# MEM_P2P_1.net
KiCad netlist of a schematic drawn in EAGLE
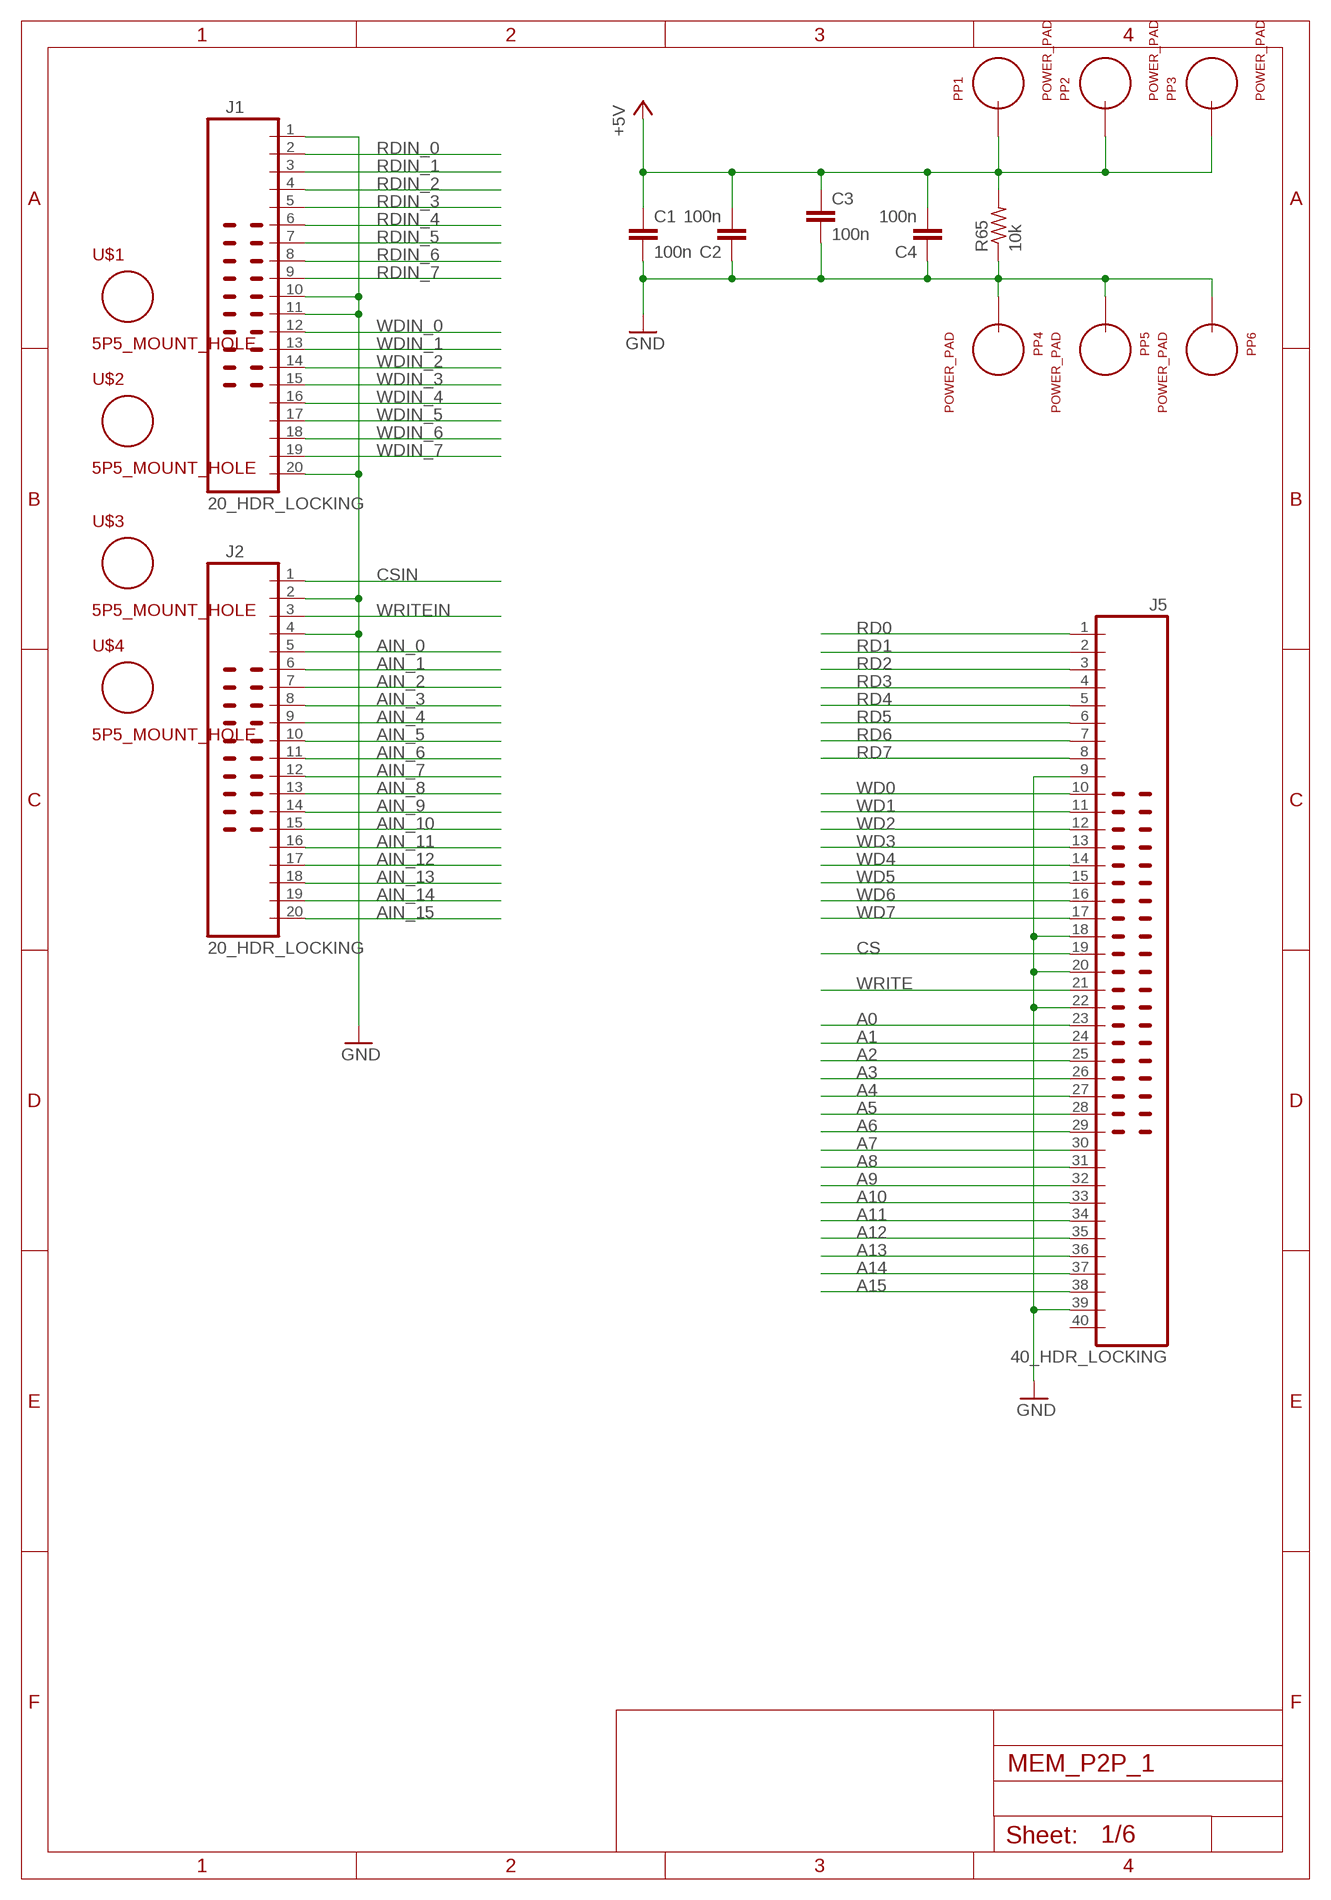
[diagram p0: schematic, sheet 1]
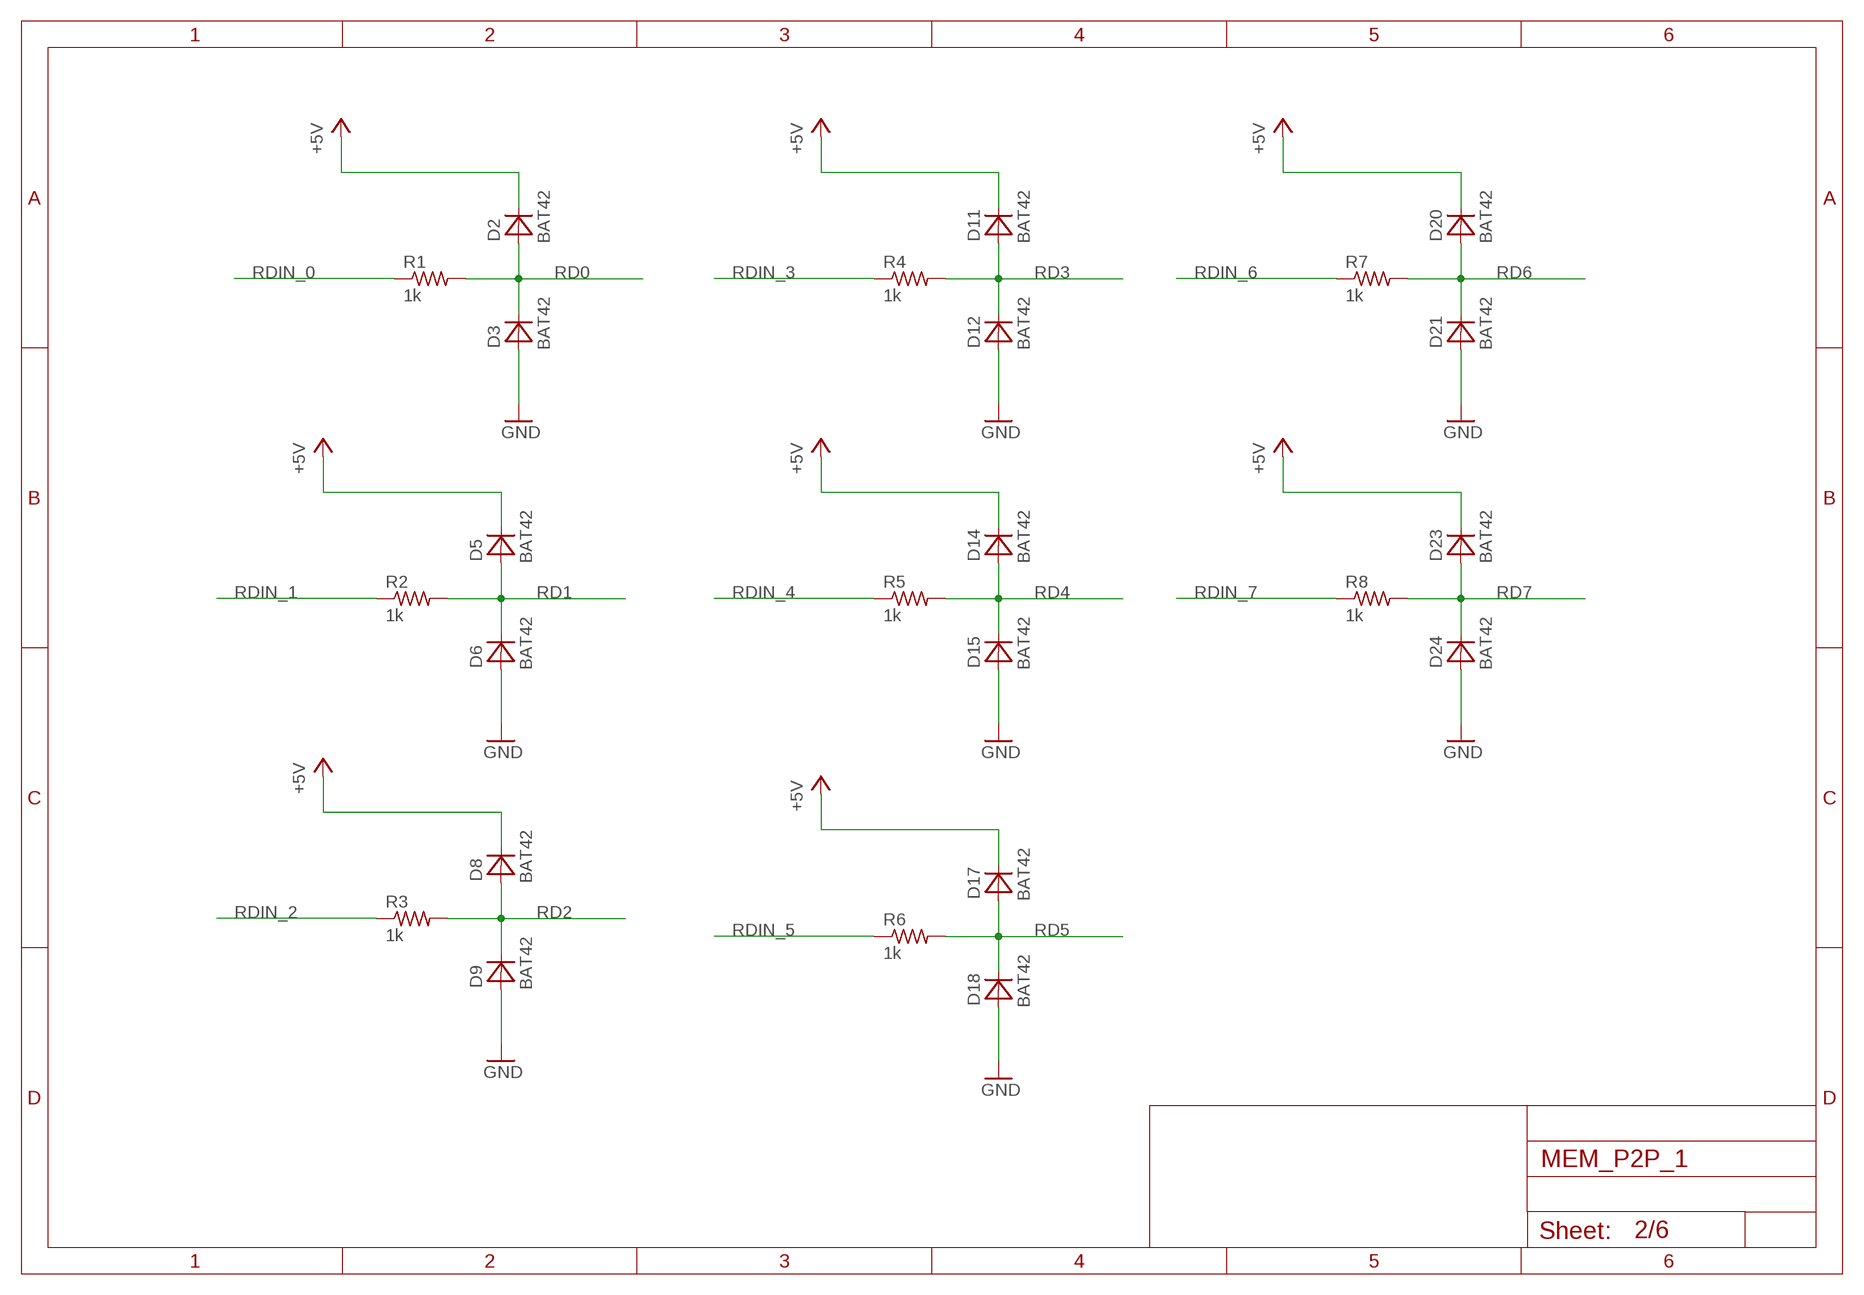
[diagram p1: schematic, sheet 2]
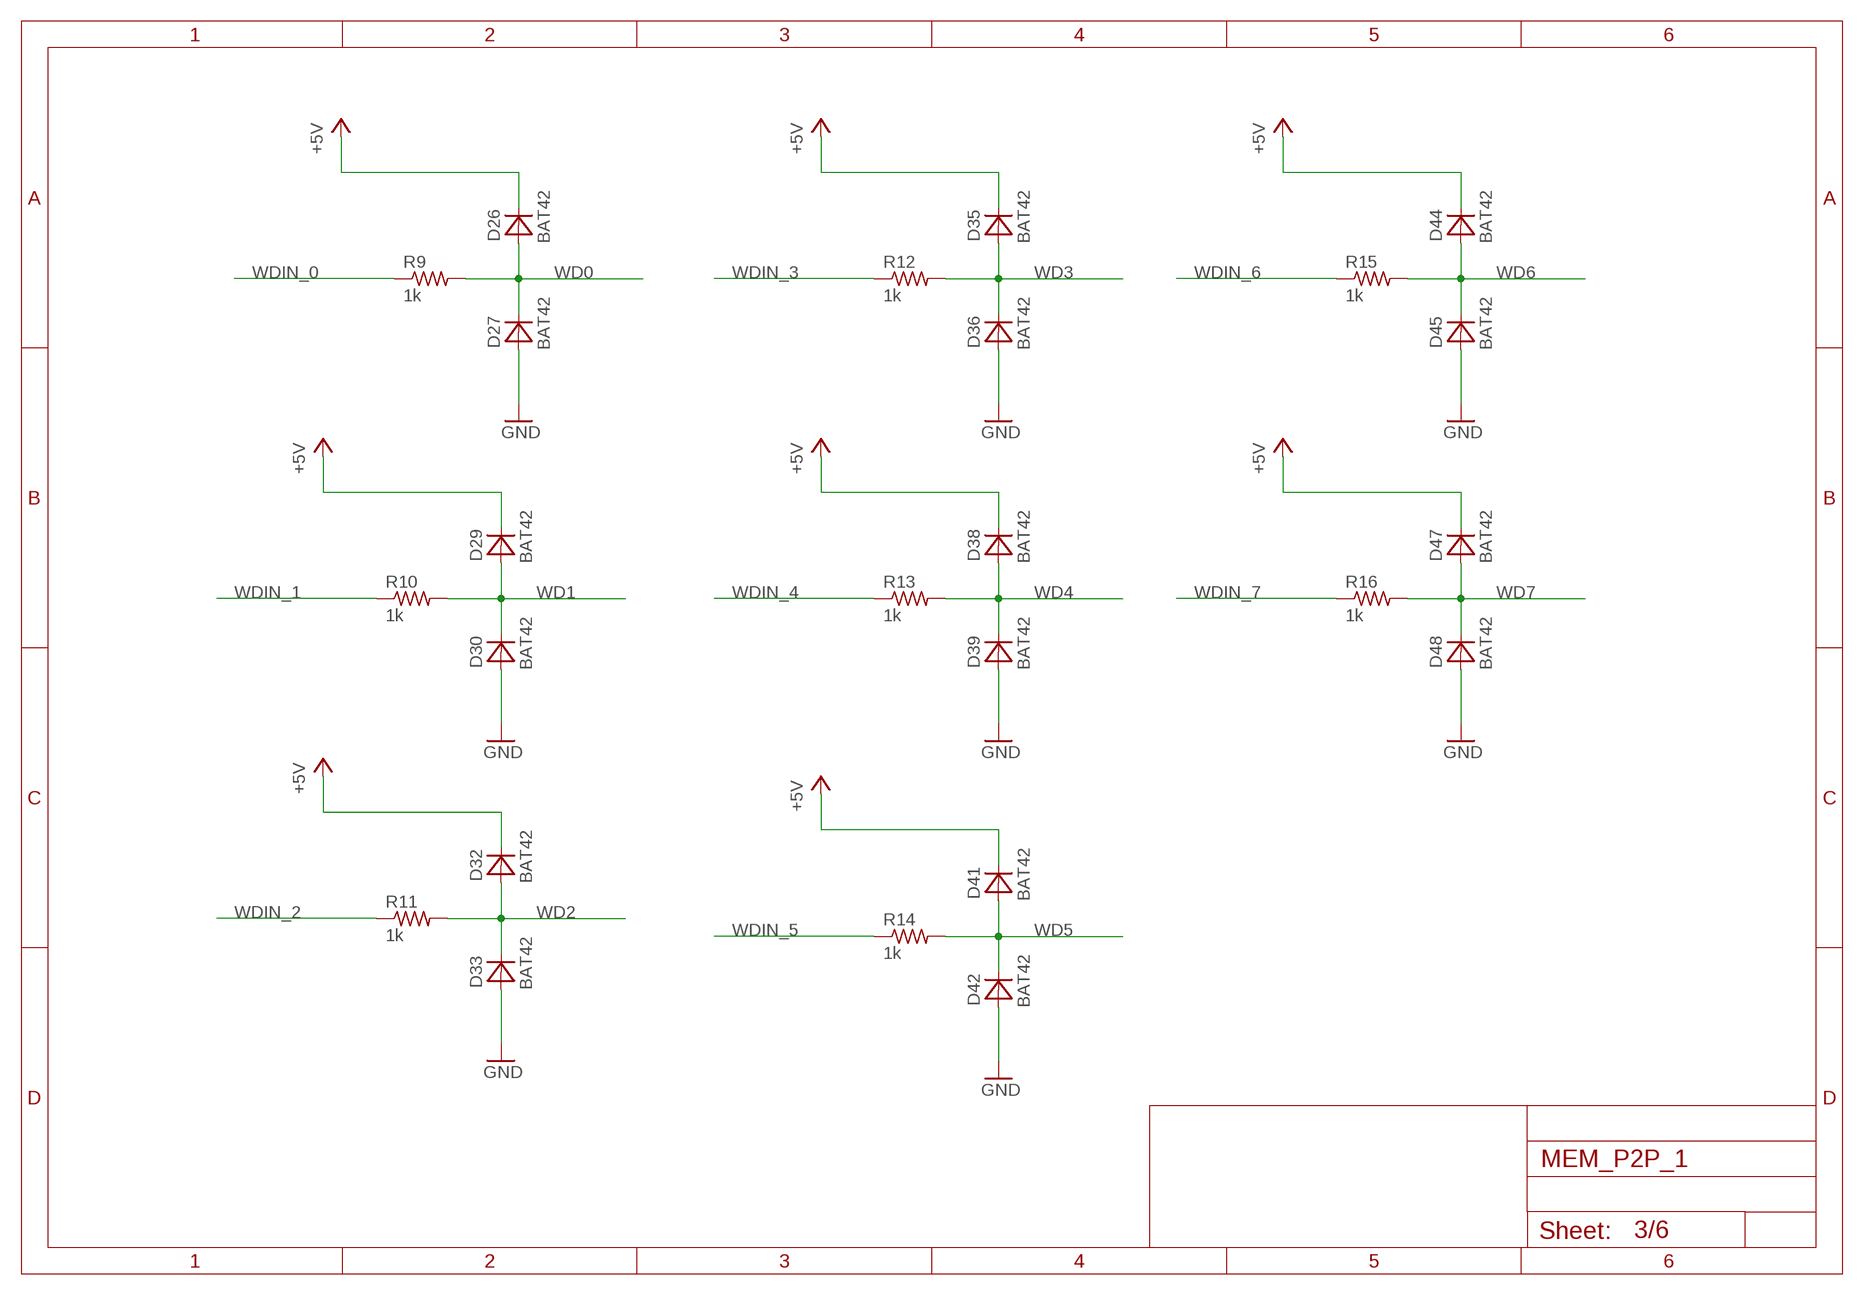
[diagram p2: schematic, sheet 3]
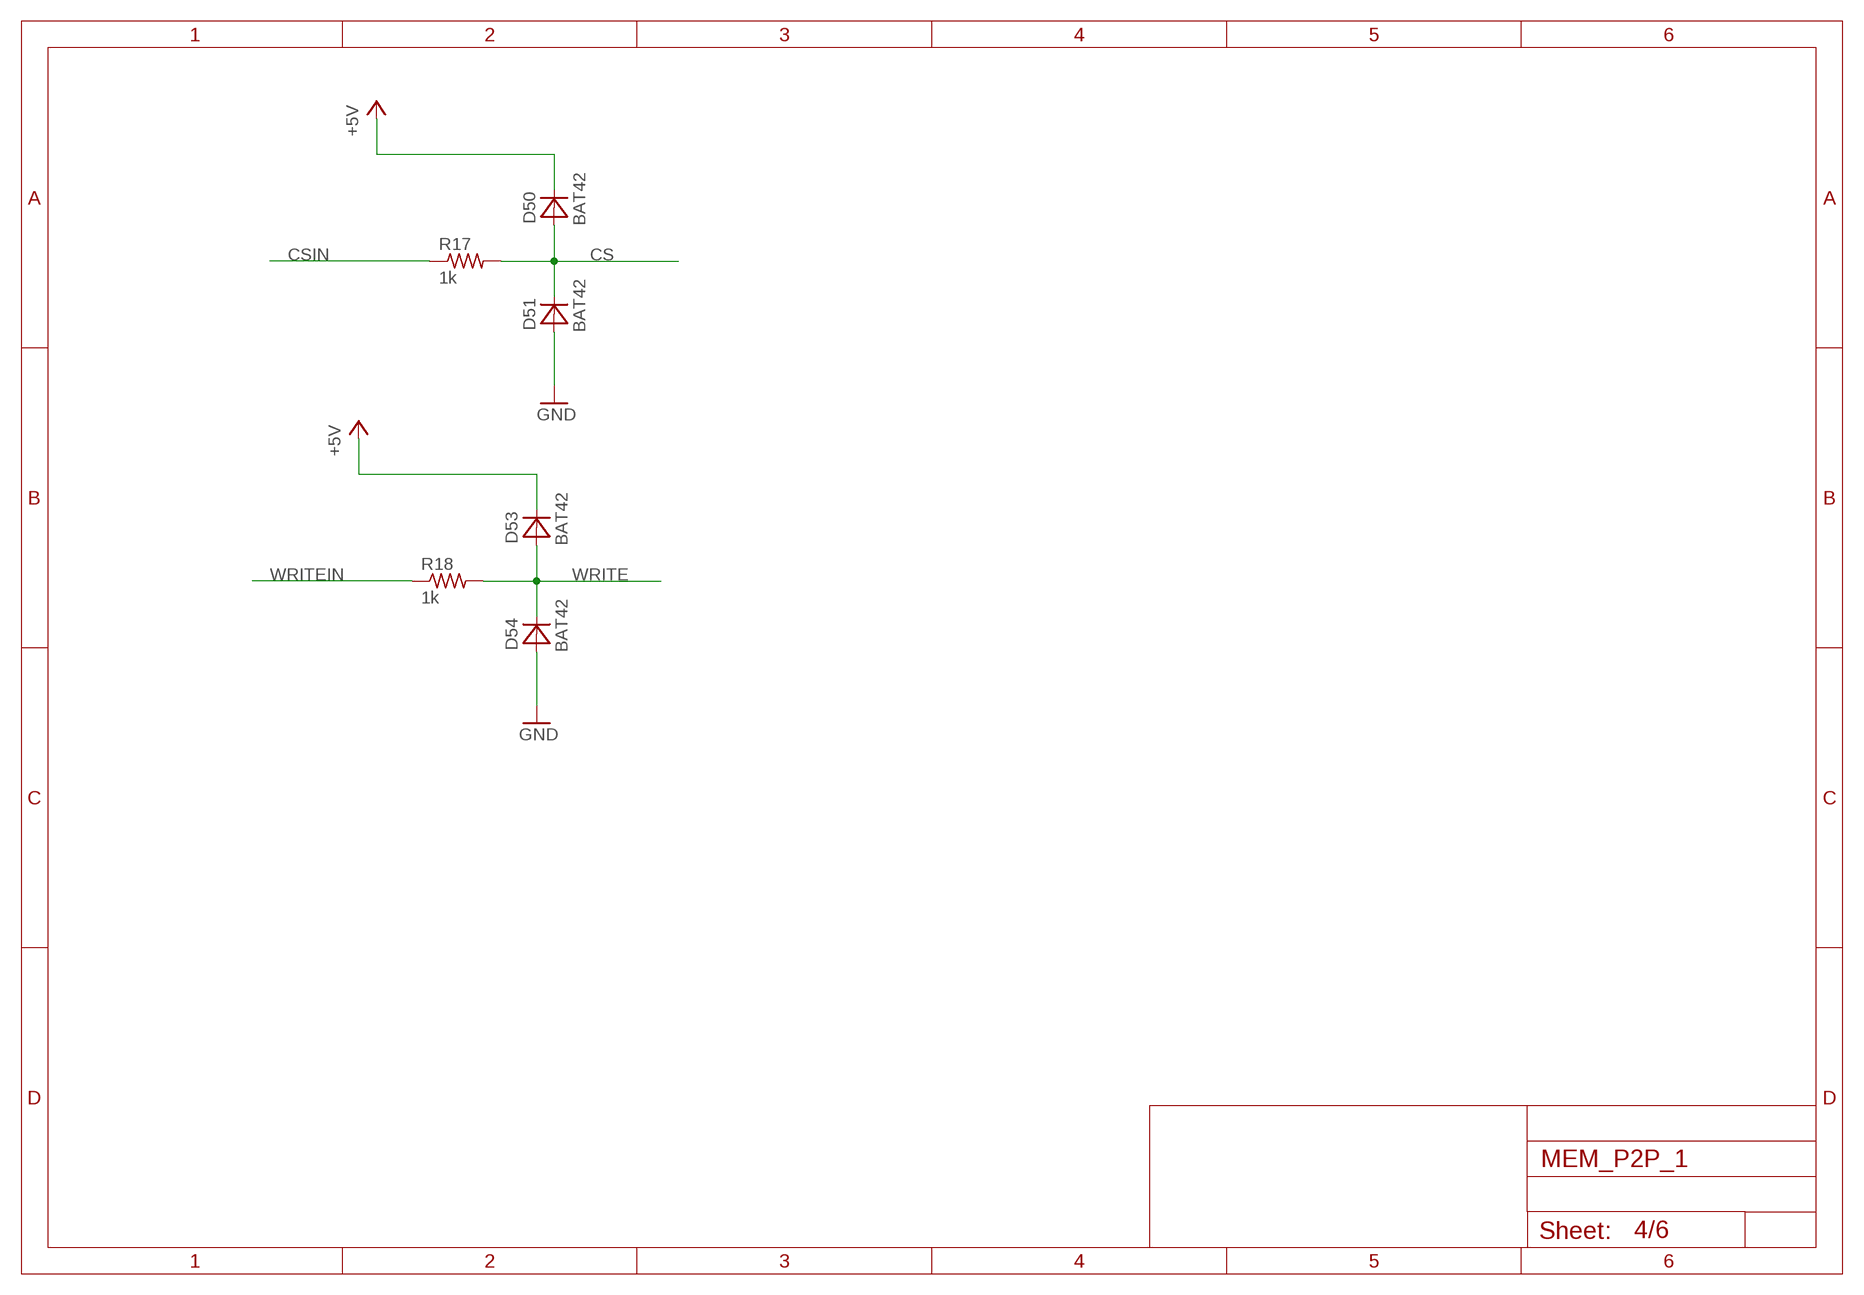
[diagram p3: schematic, sheet 4]
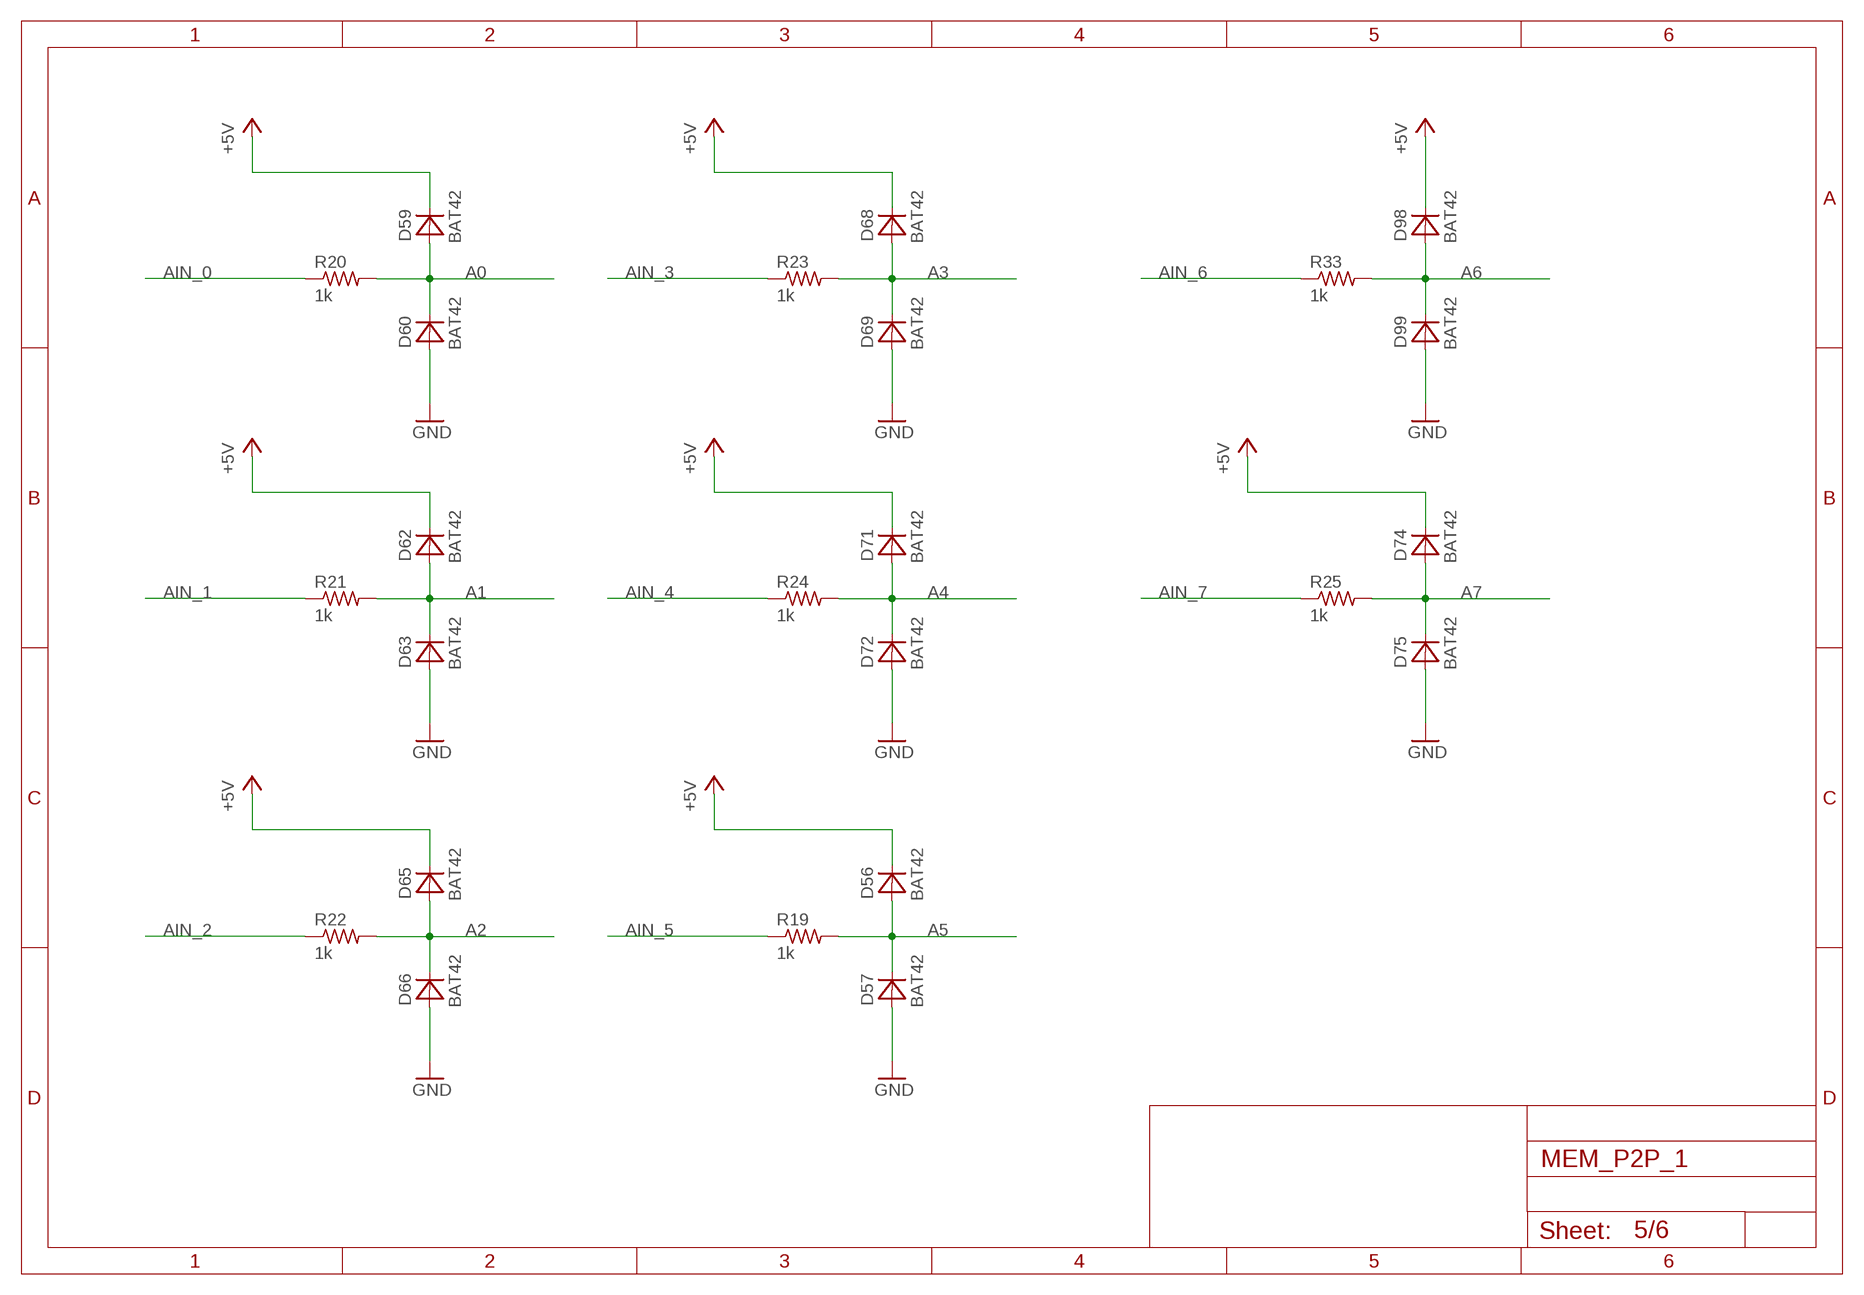
[diagram p4: schematic, sheet 5]
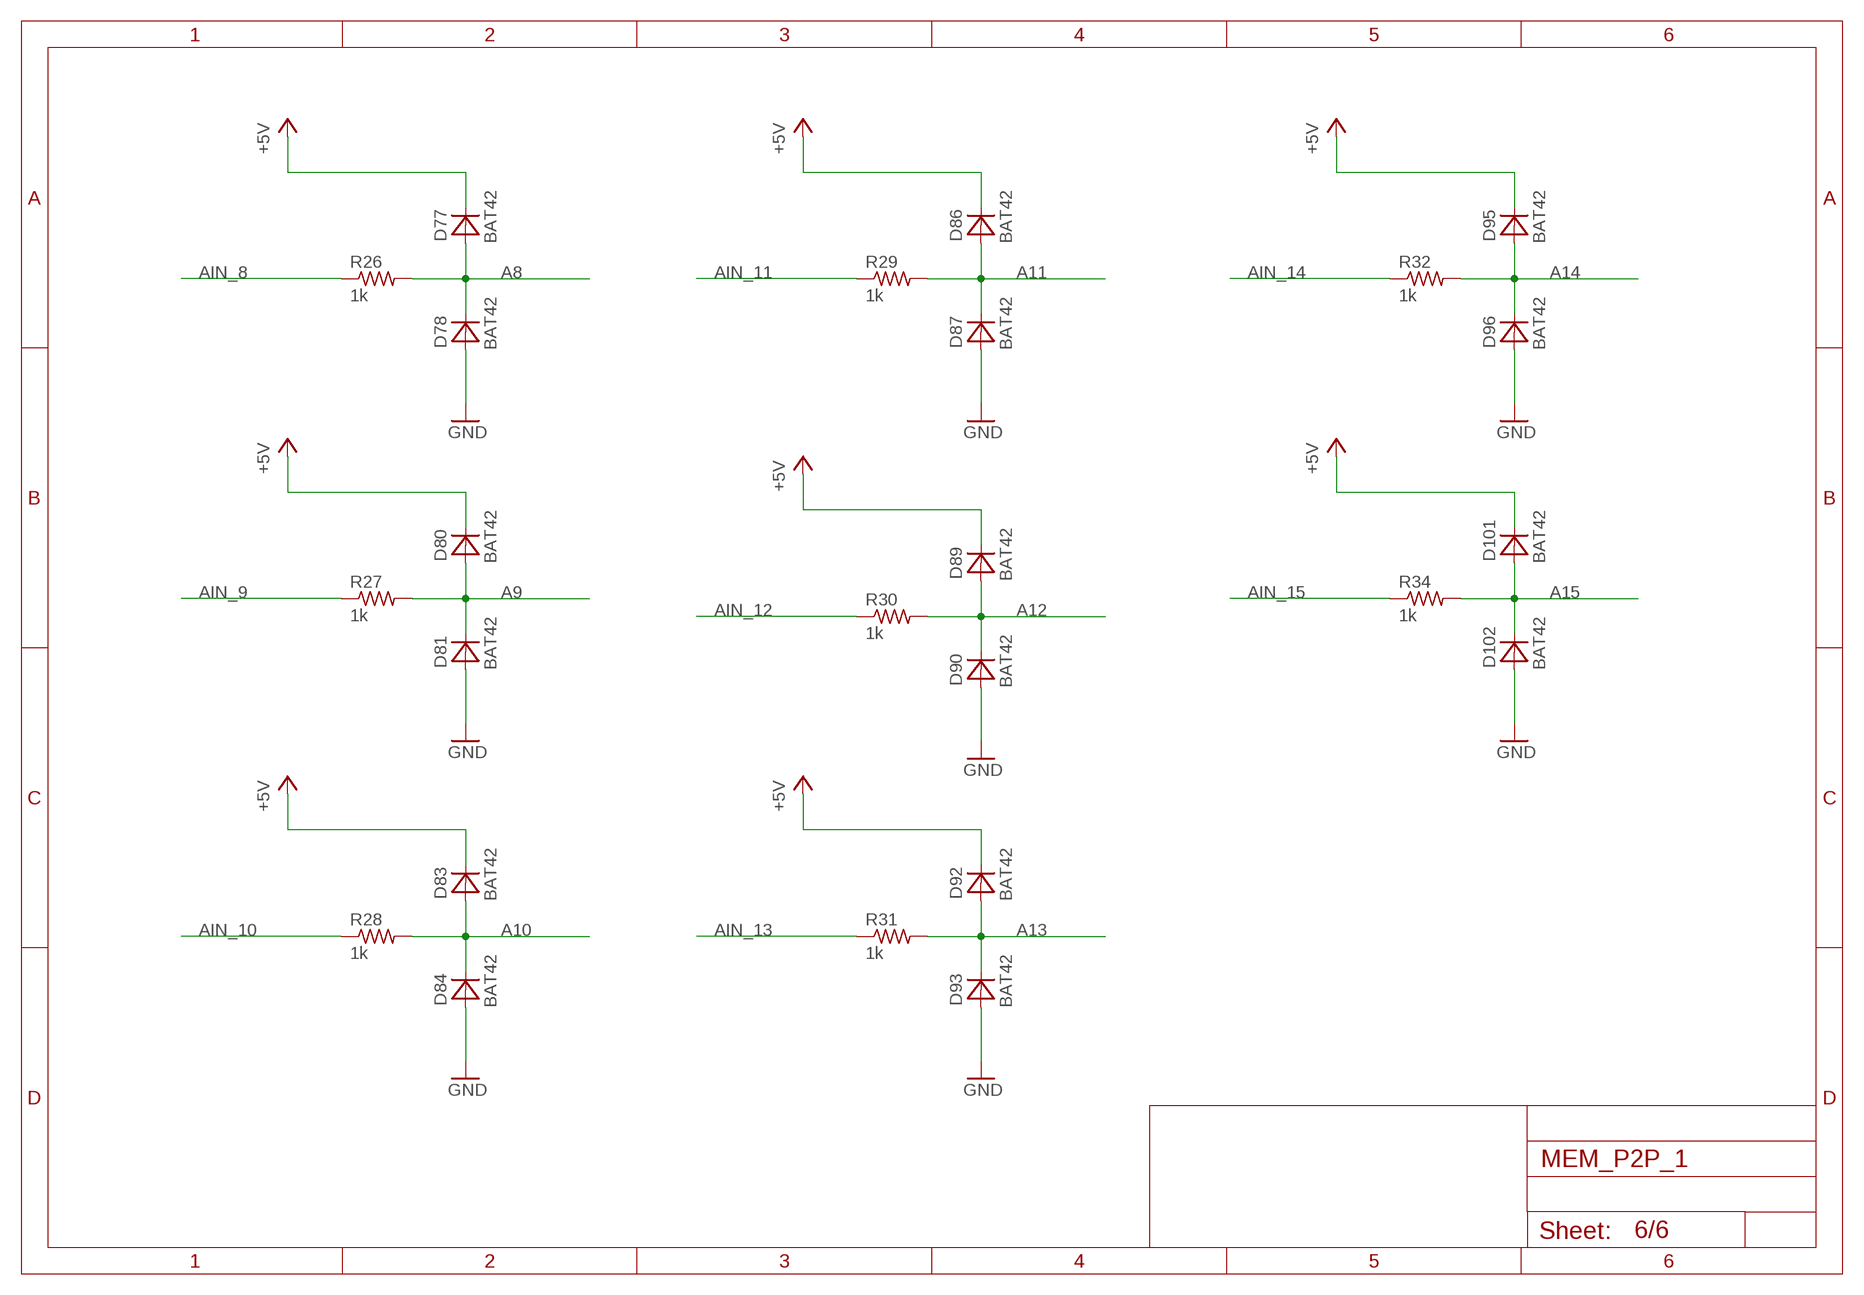
[diagram p5: schematic, sheet 6]

(export (version "E")
  (design (tool "Eeschema 10.0.6"))
  (components
    (comp (ref "D26")
      (value "BAT42")
      (footprint "eagle-import:DO34-5")
      (libsource (lib "eagle-import") (part "BAT42"))
    )
    (comp (ref "D27")
      (value "BAT42")
      (footprint "eagle-import:DO34-5")
      (libsource (lib "eagle-import") (part "BAT42"))
    )
    (comp (ref "D29")
      (value "BAT42")
      (footprint "eagle-import:DO34-5")
      (libsource (lib "eagle-import") (part "BAT42"))
    )
    (comp (ref "D30")
      (value "BAT42")
      (footprint "eagle-import:DO34-5")
      (libsource (lib "eagle-import") (part "BAT42"))
    )
    (comp (ref "D32")
      (value "BAT42")
      (footprint "eagle-import:DO34-5")
      (libsource (lib "eagle-import") (part "BAT42"))
    )
    (comp (ref "D33")
      (value "BAT42")
      (footprint "eagle-import:DO34-5")
      (libsource (lib "eagle-import") (part "BAT42"))
    )
    (comp (ref "D35")
      (value "BAT42")
      (footprint "eagle-import:DO34-5")
      (libsource (lib "eagle-import") (part "BAT42"))
    )
    (comp (ref "D36")
      (value "BAT42")
      (footprint "eagle-import:DO34-5")
      (libsource (lib "eagle-import") (part "BAT42"))
    )
    (comp (ref "D38")
      (value "BAT42")
      (footprint "eagle-import:DO34-5")
      (libsource (lib "eagle-import") (part "BAT42"))
    )
    (comp (ref "D39")
      (value "BAT42")
      (footprint "eagle-import:DO34-5")
      (libsource (lib "eagle-import") (part "BAT42"))
    )
    (comp (ref "D41")
      (value "BAT42")
      (footprint "eagle-import:DO34-5")
      (libsource (lib "eagle-import") (part "BAT42"))
    )
    (comp (ref "D42")
      (value "BAT42")
      (footprint "eagle-import:DO34-5")
      (libsource (lib "eagle-import") (part "BAT42"))
    )
    (comp (ref "D44")
      (value "BAT42")
      (footprint "eagle-import:DO34-5")
      (libsource (lib "eagle-import") (part "BAT42"))
    )
    (comp (ref "D45")
      (value "BAT42")
      (footprint "eagle-import:DO34-5")
      (libsource (lib "eagle-import") (part "BAT42"))
    )
    (comp (ref "D47")
      (value "BAT42")
      (footprint "eagle-import:DO34-5")
      (libsource (lib "eagle-import") (part "BAT42"))
    )
    (comp (ref "D48")
      (value "BAT42")
      (footprint "eagle-import:DO34-5")
      (libsource (lib "eagle-import") (part "BAT42"))
    )
    (comp (ref "R9")
      (value "1k")
      (footprint "eagle-import:R_P2INCH")
      (libsource (lib "eagle-import") (part "R_P2INCH"))
    )
    (comp (ref "R10")
      (value "1k")
      (footprint "eagle-import:R_P2INCH")
      (libsource (lib "eagle-import") (part "R_P2INCH"))
    )
    (comp (ref "R11")
      (value "1k")
      (footprint "eagle-import:R_P2INCH")
      (libsource (lib "eagle-import") (part "R_P2INCH"))
    )
    (comp (ref "R12")
      (value "1k")
      (footprint "eagle-import:R_P2INCH")
      (libsource (lib "eagle-import") (part "R_P2INCH"))
    )
    (comp (ref "R13")
      (value "1k")
      (footprint "eagle-import:R_P2INCH")
      (libsource (lib "eagle-import") (part "R_P2INCH"))
    )
    (comp (ref "R14")
      (value "1k")
      (footprint "eagle-import:R_P2INCH")
      (libsource (lib "eagle-import") (part "R_P2INCH"))
    )
    (comp (ref "R15")
      (value "1k")
      (footprint "eagle-import:R_P2INCH")
      (libsource (lib "eagle-import") (part "R_P2INCH"))
    )
    (comp (ref "R16")
      (value "1k")
      (footprint "eagle-import:R_P2INCH")
      (libsource (lib "eagle-import") (part "R_P2INCH"))
    )
    (comp (ref "C1")
      (value "100n")
      (footprint "eagle-import:CAP_P2INCH")
      (libsource (lib "eagle-import") (part "C_P2INCH"))
    )
    (comp (ref "C2")
      (value "100n")
      (footprint "eagle-import:CAP_P2INCH")
      (libsource (lib "eagle-import") (part "C_P2INCH"))
    )
    (comp (ref "C3")
      (value "100n")
      (footprint "eagle-import:CAP_P2INCH")
      (libsource (lib "eagle-import") (part "C_P2INCH"))
    )
    (comp (ref "C4")
      (value "100n")
      (footprint "eagle-import:CAP_P2INCH")
      (libsource (lib "eagle-import") (part "C_P2INCH"))
    )
    (comp (ref "J1")
      (value "20_HDR_LOCKING")
      (footprint "eagle-import:20_HDR_LOCKING")
      (libsource (lib "eagle-import") (part "20_HDR_LOCKING"))
    )
    (comp (ref "J2")
      (value "20_HDR_LOCKING")
      (footprint "eagle-import:20_HDR_LOCKING")
      (libsource (lib "eagle-import") (part "20_HDR_LOCKING"))
    )
    (comp (ref "J5")
      (value "40_HDR_LOCKING")
      (footprint "eagle-import:40_HDR_LOCKING")
      (libsource (lib "eagle-import") (part "40_HDR_LOCKING"))
    )
    (comp (ref "PP1")
      (value "POWER_PAD")
      (footprint "eagle-import:POWER_PAD")
      (libsource (lib "eagle-import") (part "POWER_PAD"))
    )
    (comp (ref "PP2")
      (value "POWER_PAD")
      (footprint "eagle-import:POWER_PAD")
      (libsource (lib "eagle-import") (part "POWER_PAD"))
    )
    (comp (ref "PP3")
      (value "POWER_PAD")
      (footprint "eagle-import:POWER_PAD")
      (libsource (lib "eagle-import") (part "POWER_PAD"))
    )
    (comp (ref "PP4")
      (value "POWER_PAD")
      (footprint "eagle-import:POWER_PAD")
      (libsource (lib "eagle-import") (part "POWER_PAD"))
    )
    (comp (ref "PP5")
      (value "POWER_PAD")
      (footprint "eagle-import:POWER_PAD")
      (libsource (lib "eagle-import") (part "POWER_PAD"))
    )
    (comp (ref "PP6")
      (value "POWER_PAD")
      (footprint "eagle-import:POWER_PAD")
      (libsource (lib "eagle-import") (part "POWER_PAD"))
    )
    (comp (ref "R65")
      (value "10k")
      (footprint "eagle-import:R_P2INCH")
      (libsource (lib "eagle-import") (part "R_P2INCH"))
    )
    (comp (ref "U$1")
      (value "5P5_MOUNT_HOLE")
      (footprint "eagle-import:5P5M_HOLE")
      (libsource (lib "eagle-import") (part "5P5_MOUNT_HOLE"))
    )
    (comp (ref "U$2")
      (value "5P5_MOUNT_HOLE")
      (footprint "eagle-import:5P5M_HOLE")
      (libsource (lib "eagle-import") (part "5P5_MOUNT_HOLE"))
    )
    (comp (ref "U$3")
      (value "5P5_MOUNT_HOLE")
      (footprint "eagle-import:5P5M_HOLE")
      (libsource (lib "eagle-import") (part "5P5_MOUNT_HOLE"))
    )
    (comp (ref "U$4")
      (value "5P5_MOUNT_HOLE")
      (footprint "eagle-import:5P5M_HOLE")
      (libsource (lib "eagle-import") (part "5P5_MOUNT_HOLE"))
    )
    (comp (ref "D56")
      (value "BAT42")
      (footprint "eagle-import:DO34-5")
      (libsource (lib "eagle-import") (part "BAT42"))
    )
    (comp (ref "D57")
      (value "BAT42")
      (footprint "eagle-import:DO34-5")
      (libsource (lib "eagle-import") (part "BAT42"))
    )
    (comp (ref "D59")
      (value "BAT42")
      (footprint "eagle-import:DO34-5")
      (libsource (lib "eagle-import") (part "BAT42"))
    )
    (comp (ref "D60")
      (value "BAT42")
      (footprint "eagle-import:DO34-5")
      (libsource (lib "eagle-import") (part "BAT42"))
    )
    (comp (ref "D62")
      (value "BAT42")
      (footprint "eagle-import:DO34-5")
      (libsource (lib "eagle-import") (part "BAT42"))
    )
    (comp (ref "D63")
      (value "BAT42")
      (footprint "eagle-import:DO34-5")
      (libsource (lib "eagle-import") (part "BAT42"))
    )
    (comp (ref "D65")
      (value "BAT42")
      (footprint "eagle-import:DO34-5")
      (libsource (lib "eagle-import") (part "BAT42"))
    )
    (comp (ref "D66")
      (value "BAT42")
      (footprint "eagle-import:DO34-5")
      (libsource (lib "eagle-import") (part "BAT42"))
    )
    (comp (ref "D68")
      (value "BAT42")
      (footprint "eagle-import:DO34-5")
      (libsource (lib "eagle-import") (part "BAT42"))
    )
    (comp (ref "D69")
      (value "BAT42")
      (footprint "eagle-import:DO34-5")
      (libsource (lib "eagle-import") (part "BAT42"))
    )
    (comp (ref "D71")
      (value "BAT42")
      (footprint "eagle-import:DO34-5")
      (libsource (lib "eagle-import") (part "BAT42"))
    )
    (comp (ref "D72")
      (value "BAT42")
      (footprint "eagle-import:DO34-5")
      (libsource (lib "eagle-import") (part "BAT42"))
    )
    (comp (ref "D74")
      (value "BAT42")
      (footprint "eagle-import:DO34-5")
      (libsource (lib "eagle-import") (part "BAT42"))
    )
    (comp (ref "D75")
      (value "BAT42")
      (footprint "eagle-import:DO34-5")
      (libsource (lib "eagle-import") (part "BAT42"))
    )
    (comp (ref "D98")
      (value "BAT42")
      (footprint "eagle-import:DO34-5")
      (libsource (lib "eagle-import") (part "BAT42"))
    )
    (comp (ref "D99")
      (value "BAT42")
      (footprint "eagle-import:DO34-5")
      (libsource (lib "eagle-import") (part "BAT42"))
    )
    (comp (ref "R19")
      (value "1k")
      (footprint "eagle-import:R_P2INCH")
      (libsource (lib "eagle-import") (part "R_P2INCH"))
    )
    (comp (ref "R20")
      (value "1k")
      (footprint "eagle-import:R_P2INCH")
      (libsource (lib "eagle-import") (part "R_P2INCH"))
    )
    (comp (ref "R21")
      (value "1k")
      (footprint "eagle-import:R_P2INCH")
      (libsource (lib "eagle-import") (part "R_P2INCH"))
    )
    (comp (ref "R22")
      (value "1k")
      (footprint "eagle-import:R_P2INCH")
      (libsource (lib "eagle-import") (part "R_P2INCH"))
    )
    (comp (ref "R23")
      (value "1k")
      (footprint "eagle-import:R_P2INCH")
      (libsource (lib "eagle-import") (part "R_P2INCH"))
    )
    (comp (ref "R24")
      (value "1k")
      (footprint "eagle-import:R_P2INCH")
      (libsource (lib "eagle-import") (part "R_P2INCH"))
    )
    (comp (ref "R25")
      (value "1k")
      (footprint "eagle-import:R_P2INCH")
      (libsource (lib "eagle-import") (part "R_P2INCH"))
    )
    (comp (ref "R33")
      (value "1k")
      (footprint "eagle-import:R_P2INCH")
      (libsource (lib "eagle-import") (part "R_P2INCH"))
    )
    (comp (ref "D2")
      (value "BAT42")
      (footprint "eagle-import:DO34-5")
      (libsource (lib "eagle-import") (part "BAT42"))
    )
    (comp (ref "D3")
      (value "BAT42")
      (footprint "eagle-import:DO34-5")
      (libsource (lib "eagle-import") (part "BAT42"))
    )
    (comp (ref "D5")
      (value "BAT42")
      (footprint "eagle-import:DO34-5")
      (libsource (lib "eagle-import") (part "BAT42"))
    )
    (comp (ref "D6")
      (value "BAT42")
      (footprint "eagle-import:DO34-5")
      (libsource (lib "eagle-import") (part "BAT42"))
    )
    (comp (ref "D8")
      (value "BAT42")
      (footprint "eagle-import:DO34-5")
      (libsource (lib "eagle-import") (part "BAT42"))
    )
    (comp (ref "D9")
      (value "BAT42")
      (footprint "eagle-import:DO34-5")
      (libsource (lib "eagle-import") (part "BAT42"))
    )
    (comp (ref "D11")
      (value "BAT42")
      (footprint "eagle-import:DO34-5")
      (libsource (lib "eagle-import") (part "BAT42"))
    )
    (comp (ref "D12")
      (value "BAT42")
      (footprint "eagle-import:DO34-5")
      (libsource (lib "eagle-import") (part "BAT42"))
    )
    (comp (ref "D14")
      (value "BAT42")
      (footprint "eagle-import:DO34-5")
      (libsource (lib "eagle-import") (part "BAT42"))
    )
    (comp (ref "D15")
      (value "BAT42")
      (footprint "eagle-import:DO34-5")
      (libsource (lib "eagle-import") (part "BAT42"))
    )
    (comp (ref "D17")
      (value "BAT42")
      (footprint "eagle-import:DO34-5")
      (libsource (lib "eagle-import") (part "BAT42"))
    )
    (comp (ref "D18")
      (value "BAT42")
      (footprint "eagle-import:DO34-5")
      (libsource (lib "eagle-import") (part "BAT42"))
    )
    (comp (ref "D20")
      (value "BAT42")
      (footprint "eagle-import:DO34-5")
      (libsource (lib "eagle-import") (part "BAT42"))
    )
    (comp (ref "D21")
      (value "BAT42")
      (footprint "eagle-import:DO34-5")
      (libsource (lib "eagle-import") (part "BAT42"))
    )
    (comp (ref "D23")
      (value "BAT42")
      (footprint "eagle-import:DO34-5")
      (libsource (lib "eagle-import") (part "BAT42"))
    )
    (comp (ref "D24")
      (value "BAT42")
      (footprint "eagle-import:DO34-5")
      (libsource (lib "eagle-import") (part "BAT42"))
    )
    (comp (ref "R1")
      (value "1k")
      (footprint "eagle-import:R_P2INCH")
      (libsource (lib "eagle-import") (part "R_P2INCH"))
    )
    (comp (ref "R2")
      (value "1k")
      (footprint "eagle-import:R_P2INCH")
      (libsource (lib "eagle-import") (part "R_P2INCH"))
    )
    (comp (ref "R3")
      (value "1k")
      (footprint "eagle-import:R_P2INCH")
      (libsource (lib "eagle-import") (part "R_P2INCH"))
    )
    (comp (ref "R4")
      (value "1k")
      (footprint "eagle-import:R_P2INCH")
      (libsource (lib "eagle-import") (part "R_P2INCH"))
    )
    (comp (ref "R5")
      (value "1k")
      (footprint "eagle-import:R_P2INCH")
      (libsource (lib "eagle-import") (part "R_P2INCH"))
    )
    (comp (ref "R6")
      (value "1k")
      (footprint "eagle-import:R_P2INCH")
      (libsource (lib "eagle-import") (part "R_P2INCH"))
    )
    (comp (ref "R7")
      (value "1k")
      (footprint "eagle-import:R_P2INCH")
      (libsource (lib "eagle-import") (part "R_P2INCH"))
    )
    (comp (ref "R8")
      (value "1k")
      (footprint "eagle-import:R_P2INCH")
      (libsource (lib "eagle-import") (part "R_P2INCH"))
    )
    (comp (ref "D50")
      (value "BAT42")
      (footprint "eagle-import:DO34-5")
      (libsource (lib "eagle-import") (part "BAT42"))
    )
    (comp (ref "D51")
      (value "BAT42")
      (footprint "eagle-import:DO34-5")
      (libsource (lib "eagle-import") (part "BAT42"))
    )
    (comp (ref "D53")
      (value "BAT42")
      (footprint "eagle-import:DO34-5")
      (libsource (lib "eagle-import") (part "BAT42"))
    )
    (comp (ref "D54")
      (value "BAT42")
      (footprint "eagle-import:DO34-5")
      (libsource (lib "eagle-import") (part "BAT42"))
    )
    (comp (ref "R17")
      (value "1k")
      (footprint "eagle-import:R_P2INCH")
      (libsource (lib "eagle-import") (part "R_P2INCH"))
    )
    (comp (ref "R18")
      (value "1k")
      (footprint "eagle-import:R_P2INCH")
      (libsource (lib "eagle-import") (part "R_P2INCH"))
    )
    (comp (ref "D77")
      (value "BAT42")
      (footprint "eagle-import:DO34-5")
      (libsource (lib "eagle-import") (part "BAT42"))
    )
    (comp (ref "D78")
      (value "BAT42")
      (footprint "eagle-import:DO34-5")
      (libsource (lib "eagle-import") (part "BAT42"))
    )
    (comp (ref "D80")
      (value "BAT42")
      (footprint "eagle-import:DO34-5")
      (libsource (lib "eagle-import") (part "BAT42"))
    )
    (comp (ref "D81")
      (value "BAT42")
      (footprint "eagle-import:DO34-5")
      (libsource (lib "eagle-import") (part "BAT42"))
    )
    (comp (ref "D83")
      (value "BAT42")
      (footprint "eagle-import:DO34-5")
      (libsource (lib "eagle-import") (part "BAT42"))
    )
    (comp (ref "D84")
      (value "BAT42")
      (footprint "eagle-import:DO34-5")
      (libsource (lib "eagle-import") (part "BAT42"))
    )
    (comp (ref "D86")
      (value "BAT42")
      (footprint "eagle-import:DO34-5")
      (libsource (lib "eagle-import") (part "BAT42"))
    )
    (comp (ref "D87")
      (value "BAT42")
      (footprint "eagle-import:DO34-5")
      (libsource (lib "eagle-import") (part "BAT42"))
    )
    (comp (ref "D89")
      (value "BAT42")
      (footprint "eagle-import:DO34-5")
      (libsource (lib "eagle-import") (part "BAT42"))
    )
    (comp (ref "D90")
      (value "BAT42")
      (footprint "eagle-import:DO34-5")
      (libsource (lib "eagle-import") (part "BAT42"))
    )
    (comp (ref "D92")
      (value "BAT42")
      (footprint "eagle-import:DO34-5")
      (libsource (lib "eagle-import") (part "BAT42"))
    )
    (comp (ref "D93")
      (value "BAT42")
      (footprint "eagle-import:DO34-5")
      (libsource (lib "eagle-import") (part "BAT42"))
    )
    (comp (ref "D95")
      (value "BAT42")
      (footprint "eagle-import:DO34-5")
      (libsource (lib "eagle-import") (part "BAT42"))
    )
    (comp (ref "D96")
      (value "BAT42")
      (footprint "eagle-import:DO34-5")
      (libsource (lib "eagle-import") (part "BAT42"))
    )
    (comp (ref "D101")
      (value "BAT42")
      (footprint "eagle-import:DO34-5")
      (libsource (lib "eagle-import") (part "BAT42"))
    )
    (comp (ref "D102")
      (value "BAT42")
      (footprint "eagle-import:DO34-5")
      (libsource (lib "eagle-import") (part "BAT42"))
    )
    (comp (ref "R26")
      (value "1k")
      (footprint "eagle-import:R_P2INCH")
      (libsource (lib "eagle-import") (part "R_P2INCH"))
    )
    (comp (ref "R27")
      (value "1k")
      (footprint "eagle-import:R_P2INCH")
      (libsource (lib "eagle-import") (part "R_P2INCH"))
    )
    (comp (ref "R28")
      (value "1k")
      (footprint "eagle-import:R_P2INCH")
      (libsource (lib "eagle-import") (part "R_P2INCH"))
    )
    (comp (ref "R29")
      (value "1k")
      (footprint "eagle-import:R_P2INCH")
      (libsource (lib "eagle-import") (part "R_P2INCH"))
    )
    (comp (ref "R30")
      (value "1k")
      (footprint "eagle-import:R_P2INCH")
      (libsource (lib "eagle-import") (part "R_P2INCH"))
    )
    (comp (ref "R31")
      (value "1k")
      (footprint "eagle-import:R_P2INCH")
      (libsource (lib "eagle-import") (part "R_P2INCH"))
    )
    (comp (ref "R32")
      (value "1k")
      (footprint "eagle-import:R_P2INCH")
      (libsource (lib "eagle-import") (part "R_P2INCH"))
    )
    (comp (ref "R34")
      (value "1k")
      (footprint "eagle-import:R_P2INCH")
      (libsource (lib "eagle-import") (part "R_P2INCH"))
    )
  )
  (nets
    (net (code "1") (name "+5V") (class "Default")
      (node (ref "C1") (pin "1") (pinfunction "1_1") (pintype "passive"))
      (node (ref "C2") (pin "2") (pinfunction "2_2") (pintype "passive"))
      (node (ref "C3") (pin "1") (pinfunction "1_1") (pintype "passive"))
      (node (ref "C4") (pin "2") (pinfunction "2_2") (pintype "passive"))
      (node (ref "D101") (pin "C") (pinfunction "C_C") (pintype "passive"))
      (node (ref "D11") (pin "C") (pinfunction "C_C") (pintype "passive"))
      (node (ref "D14") (pin "C") (pinfunction "C_C") (pintype "passive"))
      (node (ref "D17") (pin "C") (pinfunction "C_C") (pintype "passive"))
      (node (ref "D2") (pin "C") (pinfunction "C_C") (pintype "passive"))
      (node (ref "D20") (pin "C") (pinfunction "C_C") (pintype "passive"))
      (node (ref "D23") (pin "C") (pinfunction "C_C") (pintype "passive"))
      (node (ref "D26") (pin "C") (pinfunction "C_C") (pintype "passive"))
      (node (ref "D29") (pin "C") (pinfunction "C_C") (pintype "passive"))
      (node (ref "D32") (pin "C") (pinfunction "C_C") (pintype "passive"))
      (node (ref "D35") (pin "C") (pinfunction "C_C") (pintype "passive"))
      (node (ref "D38") (pin "C") (pinfunction "C_C") (pintype "passive"))
      (node (ref "D41") (pin "C") (pinfunction "C_C") (pintype "passive"))
      (node (ref "D44") (pin "C") (pinfunction "C_C") (pintype "passive"))
      (node (ref "D47") (pin "C") (pinfunction "C_C") (pintype "passive"))
      (node (ref "D5") (pin "C") (pinfunction "C_C") (pintype "passive"))
      (node (ref "D50") (pin "C") (pinfunction "C_C") (pintype "passive"))
      (node (ref "D53") (pin "C") (pinfunction "C_C") (pintype "passive"))
      (node (ref "D56") (pin "C") (pinfunction "C_C") (pintype "passive"))
      (node (ref "D59") (pin "C") (pinfunction "C_C") (pintype "passive"))
      (node (ref "D62") (pin "C") (pinfunction "C_C") (pintype "passive"))
      (node (ref "D65") (pin "C") (pinfunction "C_C") (pintype "passive"))
      (node (ref "D68") (pin "C") (pinfunction "C_C") (pintype "passive"))
      (node (ref "D71") (pin "C") (pinfunction "C_C") (pintype "passive"))
      (node (ref "D74") (pin "C") (pinfunction "C_C") (pintype "passive"))
      (node (ref "D77") (pin "C") (pinfunction "C_C") (pintype "passive"))
      (node (ref "D8") (pin "C") (pinfunction "C_C") (pintype "passive"))
      (node (ref "D80") (pin "C") (pinfunction "C_C") (pintype "passive"))
      (node (ref "D83") (pin "C") (pinfunction "C_C") (pintype "passive"))
      (node (ref "D86") (pin "C") (pinfunction "C_C") (pintype "passive"))
      (node (ref "D89") (pin "C") (pinfunction "C_C") (pintype "passive"))
      (node (ref "D92") (pin "C") (pinfunction "C_C") (pintype "passive"))
      (node (ref "D95") (pin "C") (pinfunction "C_C") (pintype "passive"))
      (node (ref "D98") (pin "C") (pinfunction "C_C") (pintype "passive"))
      (node (ref "PP1") (pin "1") (pinfunction "P$1_1") (pintype "bidirectional"))
      (node (ref "PP2") (pin "1") (pinfunction "P$1_1") (pintype "bidirectional"))
      (node (ref "PP3") (pin "1") (pinfunction "P$1_1") (pintype "bidirectional"))
      (node (ref "R65") (pin "2") (pinfunction "2_2") (pintype "passive"))
    )
    (net (code "2") (name "A0") (class "Default")
      (node (ref "D59") (pin "A") (pinfunction "A_A") (pintype "passive"))
      (node (ref "D60") (pin "C") (pinfunction "C_C") (pintype "passive"))
      (node (ref "J5") (pin "23") (pinfunction "23_23") (pintype "bidirectional"))
      (node (ref "R20") (pin "2") (pinfunction "2_2") (pintype "passive"))
    )
    (net (code "3") (name "A1") (class "Default")
      (node (ref "D62") (pin "A") (pinfunction "A_A") (pintype "passive"))
      (node (ref "D63") (pin "C") (pinfunction "C_C") (pintype "passive"))
      (node (ref "J5") (pin "24") (pinfunction "24_24") (pintype "bidirectional"))
      (node (ref "R21") (pin "2") (pinfunction "2_2") (pintype "passive"))
    )
    (net (code "4") (name "A2") (class "Default")
      (node (ref "D65") (pin "A") (pinfunction "A_A") (pintype "passive"))
      (node (ref "D66") (pin "C") (pinfunction "C_C") (pintype "passive"))
      (node (ref "J5") (pin "25") (pinfunction "25_25") (pintype "bidirectional"))
      (node (ref "R22") (pin "2") (pinfunction "2_2") (pintype "passive"))
    )
    (net (code "5") (name "A3") (class "Default")
      (node (ref "D68") (pin "A") (pinfunction "A_A") (pintype "passive"))
      (node (ref "D69") (pin "C") (pinfunction "C_C") (pintype "passive"))
      (node (ref "J5") (pin "26") (pinfunction "26_26") (pintype "bidirectional"))
      (node (ref "R23") (pin "2") (pinfunction "2_2") (pintype "passive"))
    )
    (net (code "6") (name "A4") (class "Default")
      (node (ref "D71") (pin "A") (pinfunction "A_A") (pintype "passive"))
      (node (ref "D72") (pin "C") (pinfunction "C_C") (pintype "passive"))
      (node (ref "J5") (pin "27") (pinfunction "27_27") (pintype "bidirectional"))
      (node (ref "R24") (pin "2") (pinfunction "2_2") (pintype "passive"))
    )
    (net (code "7") (name "A5") (class "Default")
      (node (ref "D56") (pin "A") (pinfunction "A_A") (pintype "passive"))
      (node (ref "D57") (pin "C") (pinfunction "C_C") (pintype "passive"))
      (node (ref "J5") (pin "28") (pinfunction "28_28") (pintype "bidirectional"))
      (node (ref "R19") (pin "2") (pinfunction "2_2") (pintype "passive"))
    )
    (net (code "8") (name "A6") (class "Default")
      (node (ref "D98") (pin "A") (pinfunction "A_A") (pintype "passive"))
      (node (ref "D99") (pin "C") (pinfunction "C_C") (pintype "passive"))
      (node (ref "J5") (pin "29") (pinfunction "29_29") (pintype "bidirectional"))
      (node (ref "R33") (pin "2") (pinfunction "2_2") (pintype "passive"))
    )
    (net (code "9") (name "A7") (class "Default")
      (node (ref "D74") (pin "A") (pinfunction "A_A") (pintype "passive"))
      (node (ref "D75") (pin "C") (pinfunction "C_C") (pintype "passive"))
      (node (ref "J5") (pin "30") (pinfunction "30_30") (pintype "bidirectional"))
      (node (ref "R25") (pin "2") (pinfunction "2_2") (pintype "passive"))
    )
    (net (code "10") (name "A8") (class "Default")
      (node (ref "D77") (pin "A") (pinfunction "A_A") (pintype "passive"))
      (node (ref "D78") (pin "C") (pinfunction "C_C") (pintype "passive"))
      (node (ref "J5") (pin "31") (pinfunction "31_31") (pintype "bidirectional"))
      (node (ref "R26") (pin "2") (pinfunction "2_2") (pintype "passive"))
    )
    (net (code "11") (name "A9") (class "Default")
      (node (ref "D80") (pin "A") (pinfunction "A_A") (pintype "passive"))
      (node (ref "D81") (pin "C") (pinfunction "C_C") (pintype "passive"))
      (node (ref "J5") (pin "32") (pinfunction "32_32") (pintype "bidirectional"))
      (node (ref "R27") (pin "2") (pinfunction "2_2") (pintype "passive"))
    )
    (net (code "12") (name "A10") (class "Default")
      (node (ref "D83") (pin "A") (pinfunction "A_A") (pintype "passive"))
      (node (ref "D84") (pin "C") (pinfunction "C_C") (pintype "passive"))
      (node (ref "J5") (pin "33") (pinfunction "33_33") (pintype "bidirectional"))
      (node (ref "R28") (pin "2") (pinfunction "2_2") (pintype "passive"))
    )
    (net (code "13") (name "A11") (class "Default")
      (node (ref "D86") (pin "A") (pinfunction "A_A") (pintype "passive"))
      (node (ref "D87") (pin "C") (pinfunction "C_C") (pintype "passive"))
      (node (ref "J5") (pin "34") (pinfunction "34_34") (pintype "bidirectional"))
      (node (ref "R29") (pin "2") (pinfunction "2_2") (pintype "passive"))
    )
    (net (code "14") (name "A12") (class "Default")
      (node (ref "D89") (pin "A") (pinfunction "A_A") (pintype "passive"))
      (node (ref "D90") (pin "C") (pinfunction "C_C") (pintype "passive"))
      (node (ref "J5") (pin "35") (pinfunction "35_35") (pintype "bidirectional"))
      (node (ref "R30") (pin "2") (pinfunction "2_2") (pintype "passive"))
    )
    (net (code "15") (name "A13") (class "Default")
      (node (ref "D92") (pin "A") (pinfunction "A_A") (pintype "passive"))
      (node (ref "D93") (pin "C") (pinfunction "C_C") (pintype "passive"))
      (node (ref "J5") (pin "36") (pinfunction "36_36") (pintype "bidirectional"))
      (node (ref "R31") (pin "2") (pinfunction "2_2") (pintype "passive"))
    )
    (net (code "16") (name "A14") (class "Default")
      (node (ref "D95") (pin "A") (pinfunction "A_A") (pintype "passive"))
      (node (ref "D96") (pin "C") (pinfunction "C_C") (pintype "passive"))
      (node (ref "J5") (pin "37") (pinfunction "37_37") (pintype "bidirectional"))
      (node (ref "R32") (pin "2") (pinfunction "2_2") (pintype "passive"))
    )
    (net (code "17") (name "A15") (class "Default")
      (node (ref "D101") (pin "A") (pinfunction "A_A") (pintype "passive"))
      (node (ref "D102") (pin "C") (pinfunction "C_C") (pintype "passive"))
      (node (ref "J5") (pin "38") (pinfunction "38_38") (pintype "bidirectional"))
      (node (ref "R34") (pin "2") (pinfunction "2_2") (pintype "passive"))
    )
    (net (code "18") (name "AIN_0") (class "Default")
      (node (ref "J2") (pin "5") (pinfunction "5_5") (pintype "bidirectional"))
      (node (ref "R20") (pin "1") (pinfunction "1_1") (pintype "passive"))
    )
    (net (code "19") (name "AIN_1") (class "Default")
      (node (ref "J2") (pin "6") (pinfunction "6_6") (pintype "bidirectional"))
      (node (ref "R21") (pin "1") (pinfunction "1_1") (pintype "passive"))
    )
    (net (code "20") (name "AIN_2") (class "Default")
      (node (ref "J2") (pin "7") (pinfunction "7_7") (pintype "bidirectional"))
      (node (ref "R22") (pin "1") (pinfunction "1_1") (pintype "passive"))
    )
    (net (code "21") (name "AIN_3") (class "Default")
      (node (ref "J2") (pin "8") (pinfunction "8_8") (pintype "bidirectional"))
      (node (ref "R23") (pin "1") (pinfunction "1_1") (pintype "passive"))
    )
    (net (code "22") (name "AIN_4") (class "Default")
      (node (ref "J2") (pin "9") (pinfunction "9_9") (pintype "bidirectional"))
      (node (ref "R24") (pin "1") (pinfunction "1_1") (pintype "passive"))
    )
    (net (code "23") (name "AIN_5") (class "Default")
      (node (ref "J2") (pin "10") (pinfunction "10_10") (pintype "bidirectional"))
      (node (ref "R19") (pin "1") (pinfunction "1_1") (pintype "passive"))
    )
    (net (code "24") (name "AIN_6") (class "Default")
      (node (ref "J2") (pin "11") (pinfunction "11_11") (pintype "bidirectional"))
      (node (ref "R33") (pin "1") (pinfunction "1_1") (pintype "passive"))
    )
    (net (code "25") (name "AIN_7") (class "Default")
      (node (ref "J2") (pin "12") (pinfunction "12_12") (pintype "bidirectional"))
      (node (ref "R25") (pin "1") (pinfunction "1_1") (pintype "passive"))
    )
    (net (code "26") (name "AIN_8") (class "Default")
      (node (ref "J2") (pin "13") (pinfunction "13_13") (pintype "bidirectional"))
      (node (ref "R26") (pin "1") (pinfunction "1_1") (pintype "passive"))
    )
    (net (code "27") (name "AIN_9") (class "Default")
      (node (ref "J2") (pin "14") (pinfunction "14_14") (pintype "bidirectional"))
      (node (ref "R27") (pin "1") (pinfunction "1_1") (pintype "passive"))
    )
    (net (code "28") (name "AIN_10") (class "Default")
      (node (ref "J2") (pin "15") (pinfunction "15_15") (pintype "bidirectional"))
      (node (ref "R28") (pin "1") (pinfunction "1_1") (pintype "passive"))
    )
    (net (code "29") (name "AIN_11") (class "Default")
      (node (ref "J2") (pin "16") (pinfunction "16_16") (pintype "bidirectional"))
      (node (ref "R29") (pin "1") (pinfunction "1_1") (pintype "passive"))
    )
    (net (code "30") (name "AIN_12") (class "Default")
      (node (ref "J2") (pin "17") (pinfunction "17_17") (pintype "bidirectional"))
      (node (ref "R30") (pin "1") (pinfunction "1_1") (pintype "passive"))
    )
    (net (code "31") (name "AIN_13") (class "Default")
      (node (ref "J2") (pin "18") (pinfunction "18_18") (pintype "bidirectional"))
      (node (ref "R31") (pin "1") (pinfunction "1_1") (pintype "passive"))
    )
    (net (code "32") (name "AIN_14") (class "Default")
      (node (ref "J2") (pin "19") (pinfunction "19_19") (pintype "bidirectional"))
      (node (ref "R32") (pin "1") (pinfunction "1_1") (pintype "passive"))
    )
    (net (code "33") (name "AIN_15") (class "Default")
      (node (ref "J2") (pin "20") (pinfunction "20_20") (pintype "bidirectional"))
      (node (ref "R34") (pin "1") (pinfunction "1_1") (pintype "passive"))
    )
    (net (code "34") (name "CS") (class "Default")
      (node (ref "D50") (pin "A") (pinfunction "A_A") (pintype "passive"))
      (node (ref "D51") (pin "C") (pinfunction "C_C") (pintype "passive"))
      (node (ref "J5") (pin "19") (pinfunction "19_19") (pintype "bidirectional"))
      (node (ref "R17") (pin "2") (pinfunction "2_2") (pintype "passive"))
    )
    (net (code "35") (name "CSIN") (class "Default")
      (node (ref "J2") (pin "1") (pinfunction "1_1") (pintype "bidirectional"))
      (node (ref "R17") (pin "1") (pinfunction "1_1") (pintype "passive"))
    )
    (net (code "36") (name "GND") (class "Default")
      (node (ref "C1") (pin "2") (pinfunction "2_2") (pintype "passive"))
      (node (ref "C2") (pin "1") (pinfunction "1_1") (pintype "passive"))
      (node (ref "C3") (pin "2") (pinfunction "2_2") (pintype "passive"))
      (node (ref "C4") (pin "1") (pinfunction "1_1") (pintype "passive"))
      (node (ref "D102") (pin "A") (pinfunction "A_A") (pintype "passive"))
      (node (ref "D12") (pin "A") (pinfunction "A_A") (pintype "passive"))
      (node (ref "D15") (pin "A") (pinfunction "A_A") (pintype "passive"))
      (node (ref "D18") (pin "A") (pinfunction "A_A") (pintype "passive"))
      (node (ref "D21") (pin "A") (pinfunction "A_A") (pintype "passive"))
      (node (ref "D24") (pin "A") (pinfunction "A_A") (pintype "passive"))
      (node (ref "D27") (pin "A") (pinfunction "A_A") (pintype "passive"))
      (node (ref "D3") (pin "A") (pinfunction "A_A") (pintype "passive"))
      (node (ref "D30") (pin "A") (pinfunction "A_A") (pintype "passive"))
      (node (ref "D33") (pin "A") (pinfunction "A_A") (pintype "passive"))
      (node (ref "D36") (pin "A") (pinfunction "A_A") (pintype "passive"))
      (node (ref "D39") (pin "A") (pinfunction "A_A") (pintype "passive"))
      (node (ref "D42") (pin "A") (pinfunction "A_A") (pintype "passive"))
      (node (ref "D45") (pin "A") (pinfunction "A_A") (pintype "passive"))
      (node (ref "D48") (pin "A") (pinfunction "A_A") (pintype "passive"))
      (node (ref "D51") (pin "A") (pinfunction "A_A") (pintype "passive"))
      (node (ref "D54") (pin "A") (pinfunction "A_A") (pintype "passive"))
      (node (ref "D57") (pin "A") (pinfunction "A_A") (pintype "passive"))
      (node (ref "D6") (pin "A") (pinfunction "A_A") (pintype "passive"))
      (node (ref "D60") (pin "A") (pinfunction "A_A") (pintype "passive"))
      (node (ref "D63") (pin "A") (pinfunction "A_A") (pintype "passive"))
      (node (ref "D66") (pin "A") (pinfunction "A_A") (pintype "passive"))
      (node (ref "D69") (pin "A") (pinfunction "A_A") (pintype "passive"))
      (node (ref "D72") (pin "A") (pinfunction "A_A") (pintype "passive"))
      (node (ref "D75") (pin "A") (pinfunction "A_A") (pintype "passive"))
      (node (ref "D78") (pin "A") (pinfunction "A_A") (pintype "passive"))
      (node (ref "D81") (pin "A") (pinfunction "A_A") (pintype "passive"))
      (node (ref "D84") (pin "A") (pinfunction "A_A") (pintype "passive"))
      (node (ref "D87") (pin "A") (pinfunction "A_A") (pintype "passive"))
      (node (ref "D9") (pin "A") (pinfunction "A_A") (pintype "passive"))
      (node (ref "D90") (pin "A") (pinfunction "A_A") (pintype "passive"))
      (node (ref "D93") (pin "A") (pinfunction "A_A") (pintype "passive"))
      (node (ref "D96") (pin "A") (pinfunction "A_A") (pintype "passive"))
      (node (ref "D99") (pin "A") (pinfunction "A_A") (pintype "passive"))
      (node (ref "J1") (pin "1") (pinfunction "1_1") (pintype "bidirectional"))
      (node (ref "J1") (pin "10") (pinfunction "10_10") (pintype "bidirectional"))
      (node (ref "J1") (pin "11") (pinfunction "11_11") (pintype "bidirectional"))
      (node (ref "J1") (pin "20") (pinfunction "20_20") (pintype "bidirectional"))
      (node (ref "J2") (pin "2") (pinfunction "2_2") (pintype "bidirectional"))
      (node (ref "J2") (pin "4") (pinfunction "4_4") (pintype "bidirectional"))
      (node (ref "J5") (pin "18") (pinfunction "18_18") (pintype "bidirectional"))
      (node (ref "J5") (pin "20") (pinfunction "20_20") (pintype "bidirectional"))
      (node (ref "J5") (pin "22") (pinfunction "22_22") (pintype "bidirectional"))
      (node (ref "J5") (pin "39") (pinfunction "39_39") (pintype "bidirectional"))
      (node (ref "J5") (pin "9") (pinfunction "9_9") (pintype "bidirectional"))
      (node (ref "PP4") (pin "1") (pinfunction "P$1_1") (pintype "bidirectional"))
      (node (ref "PP5") (pin "1") (pinfunction "P$1_1") (pintype "bidirectional"))
      (node (ref "PP6") (pin "1") (pinfunction "P$1_1") (pintype "bidirectional"))
      (node (ref "R65") (pin "1") (pinfunction "1_1") (pintype "passive"))
    )
    (net (code "37") (name "RD0") (class "Default")
      (node (ref "D2") (pin "A") (pinfunction "A_A") (pintype "passive"))
      (node (ref "D3") (pin "C") (pinfunction "C_C") (pintype "passive"))
      (node (ref "J5") (pin "1") (pinfunction "1_1") (pintype "bidirectional"))
      (node (ref "R1") (pin "2") (pinfunction "2_2") (pintype "passive"))
    )
    (net (code "38") (name "RD1") (class "Default")
      (node (ref "D5") (pin "A") (pinfunction "A_A") (pintype "passive"))
      (node (ref "D6") (pin "C") (pinfunction "C_C") (pintype "passive"))
      (node (ref "J5") (pin "2") (pinfunction "2_2") (pintype "bidirectional"))
      (node (ref "R2") (pin "2") (pinfunction "2_2") (pintype "passive"))
    )
    (net (code "39") (name "RD2") (class "Default")
      (node (ref "D8") (pin "A") (pinfunction "A_A") (pintype "passive"))
      (node (ref "D9") (pin "C") (pinfunction "C_C") (pintype "passive"))
      (node (ref "J5") (pin "3") (pinfunction "3_3") (pintype "bidirectional"))
      (node (ref "R3") (pin "2") (pinfunction "2_2") (pintype "passive"))
    )
    (net (code "40") (name "RD3") (class "Default")
      (node (ref "D11") (pin "A") (pinfunction "A_A") (pintype "passive"))
      (node (ref "D12") (pin "C") (pinfunction "C_C") (pintype "passive"))
      (node (ref "J5") (pin "4") (pinfunction "4_4") (pintype "bidirectional"))
      (node (ref "R4") (pin "2") (pinfunction "2_2") (pintype "passive"))
    )
    (net (code "41") (name "RD4") (class "Default")
      (node (ref "D14") (pin "A") (pinfunction "A_A") (pintype "passive"))
      (node (ref "D15") (pin "C") (pinfunction "C_C") (pintype "passive"))
      (node (ref "J5") (pin "5") (pinfunction "5_5") (pintype "bidirectional"))
      (node (ref "R5") (pin "2") (pinfunction "2_2") (pintype "passive"))
    )
    (net (code "42") (name "RD5") (class "Default")
      (node (ref "D17") (pin "A") (pinfunction "A_A") (pintype "passive"))
      (node (ref "D18") (pin "C") (pinfunction "C_C") (pintype "passive"))
      (node (ref "J5") (pin "6") (pinfunction "6_6") (pintype "bidirectional"))
      (node (ref "R6") (pin "2") (pinfunction "2_2") (pintype "passive"))
    )
    (net (code "43") (name "RD6") (class "Default")
      (node (ref "D20") (pin "A") (pinfunction "A_A") (pintype "passive"))
      (node (ref "D21") (pin "C") (pinfunction "C_C") (pintype "passive"))
      (node (ref "J5") (pin "7") (pinfunction "7_7") (pintype "bidirectional"))
      (node (ref "R7") (pin "2") (pinfunction "2_2") (pintype "passive"))
    )
    (net (code "44") (name "RD7") (class "Default")
      (node (ref "D23") (pin "A") (pinfunction "A_A") (pintype "passive"))
      (node (ref "D24") (pin "C") (pinfunction "C_C") (pintype "passive"))
      (node (ref "J5") (pin "8") (pinfunction "8_8") (pintype "bidirectional"))
      (node (ref "R8") (pin "2") (pinfunction "2_2") (pintype "passive"))
    )
    (net (code "45") (name "RDIN_0") (class "Default")
      (node (ref "J1") (pin "2") (pinfunction "2_2") (pintype "bidirectional"))
      (node (ref "R1") (pin "1") (pinfunction "1_1") (pintype "passive"))
    )
    (net (code "46") (name "RDIN_1") (class "Default")
      (node (ref "J1") (pin "3") (pinfunction "3_3") (pintype "bidirectional"))
      (node (ref "R2") (pin "1") (pinfunction "1_1") (pintype "passive"))
    )
    (net (code "47") (name "RDIN_2") (class "Default")
      (node (ref "J1") (pin "4") (pinfunction "4_4") (pintype "bidirectional"))
      (node (ref "R3") (pin "1") (pinfunction "1_1") (pintype "passive"))
    )
    (net (code "48") (name "RDIN_3") (class "Default")
      (node (ref "J1") (pin "5") (pinfunction "5_5") (pintype "bidirectional"))
      (node (ref "R4") (pin "1") (pinfunction "1_1") (pintype "passive"))
    )
    (net (code "49") (name "RDIN_4") (class "Default")
      (node (ref "J1") (pin "6") (pinfunction "6_6") (pintype "bidirectional"))
      (node (ref "R5") (pin "1") (pinfunction "1_1") (pintype "passive"))
    )
    (net (code "50") (name "RDIN_5") (class "Default")
      (node (ref "J1") (pin "7") (pinfunction "7_7") (pintype "bidirectional"))
      (node (ref "R6") (pin "1") (pinfunction "1_1") (pintype "passive"))
    )
    (net (code "51") (name "RDIN_6") (class "Default")
      (node (ref "J1") (pin "8") (pinfunction "8_8") (pintype "bidirectional"))
      (node (ref "R7") (pin "1") (pinfunction "1_1") (pintype "passive"))
    )
    (net (code "52") (name "RDIN_7") (class "Default")
      (node (ref "J1") (pin "9") (pinfunction "9_9") (pintype "bidirectional"))
      (node (ref "R8") (pin "1") (pinfunction "1_1") (pintype "passive"))
    )
    (net (code "53") (name "WD0") (class "Default")
      (node (ref "D26") (pin "A") (pinfunction "A_A") (pintype "passive"))
      (node (ref "D27") (pin "C") (pinfunction "C_C") (pintype "passive"))
      (node (ref "J5") (pin "10") (pinfunction "10_10") (pintype "bidirectional"))
      (node (ref "R9") (pin "2") (pinfunction "2_2") (pintype "passive"))
    )
    (net (code "54") (name "WD1") (class "Default")
      (node (ref "D29") (pin "A") (pinfunction "A_A") (pintype "passive"))
      (node (ref "D30") (pin "C") (pinfunction "C_C") (pintype "passive"))
      (node (ref "J5") (pin "11") (pinfunction "11_11") (pintype "bidirectional"))
      (node (ref "R10") (pin "2") (pinfunction "2_2") (pintype "passive"))
    )
    (net (code "55") (name "WD2") (class "Default")
      (node (ref "D32") (pin "A") (pinfunction "A_A") (pintype "passive"))
      (node (ref "D33") (pin "C") (pinfunction "C_C") (pintype "passive"))
      (node (ref "J5") (pin "12") (pinfunction "12_12") (pintype "bidirectional"))
      (node (ref "R11") (pin "2") (pinfunction "2_2") (pintype "passive"))
    )
    (net (code "56") (name "WD3") (class "Default")
      (node (ref "D35") (pin "A") (pinfunction "A_A") (pintype "passive"))
      (node (ref "D36") (pin "C") (pinfunction "C_C") (pintype "passive"))
      (node (ref "J5") (pin "13") (pinfunction "13_13") (pintype "bidirectional"))
      (node (ref "R12") (pin "2") (pinfunction "2_2") (pintype "passive"))
    )
    (net (code "57") (name "WD4") (class "Default")
      (node (ref "D38") (pin "A") (pinfunction "A_A") (pintype "passive"))
      (node (ref "D39") (pin "C") (pinfunction "C_C") (pintype "passive"))
      (node (ref "J5") (pin "14") (pinfunction "14_14") (pintype "bidirectional"))
      (node (ref "R13") (pin "2") (pinfunction "2_2") (pintype "passive"))
    )
    (net (code "58") (name "WD5") (class "Default")
      (node (ref "D41") (pin "A") (pinfunction "A_A") (pintype "passive"))
      (node (ref "D42") (pin "C") (pinfunction "C_C") (pintype "passive"))
      (node (ref "J5") (pin "15") (pinfunction "15_15") (pintype "bidirectional"))
      (node (ref "R14") (pin "2") (pinfunction "2_2") (pintype "passive"))
    )
    (net (code "59") (name "WD6") (class "Default")
      (node (ref "D44") (pin "A") (pinfunction "A_A") (pintype "passive"))
      (node (ref "D45") (pin "C") (pinfunction "C_C") (pintype "passive"))
      (node (ref "J5") (pin "16") (pinfunction "16_16") (pintype "bidirectional"))
      (node (ref "R15") (pin "2") (pinfunction "2_2") (pintype "passive"))
    )
    (net (code "60") (name "WD7") (class "Default")
      (node (ref "D47") (pin "A") (pinfunction "A_A") (pintype "passive"))
      (node (ref "D48") (pin "C") (pinfunction "C_C") (pintype "passive"))
      (node (ref "J5") (pin "17") (pinfunction "17_17") (pintype "bidirectional"))
      (node (ref "R16") (pin "2") (pinfunction "2_2") (pintype "passive"))
    )
    (net (code "61") (name "WDIN_0") (class "Default")
      (node (ref "J1") (pin "12") (pinfunction "12_12") (pintype "bidirectional"))
      (node (ref "R9") (pin "1") (pinfunction "1_1") (pintype "passive"))
    )
    (net (code "62") (name "WDIN_1") (class "Default")
      (node (ref "J1") (pin "13") (pinfunction "13_13") (pintype "bidirectional"))
      (node (ref "R10") (pin "1") (pinfunction "1_1") (pintype "passive"))
    )
    (net (code "63") (name "WDIN_2") (class "Default")
      (node (ref "J1") (pin "14") (pinfunction "14_14") (pintype "bidirectional"))
      (node (ref "R11") (pin "1") (pinfunction "1_1") (pintype "passive"))
    )
    (net (code "64") (name "WDIN_3") (class "Default")
      (node (ref "J1") (pin "15") (pinfunction "15_15") (pintype "bidirectional"))
      (node (ref "R12") (pin "1") (pinfunction "1_1") (pintype "passive"))
    )
    (net (code "65") (name "WDIN_4") (class "Default")
      (node (ref "J1") (pin "16") (pinfunction "16_16") (pintype "bidirectional"))
      (node (ref "R13") (pin "1") (pinfunction "1_1") (pintype "passive"))
    )
    (net (code "66") (name "WDIN_5") (class "Default")
      (node (ref "J1") (pin "17") (pinfunction "17_17") (pintype "bidirectional"))
      (node (ref "R14") (pin "1") (pinfunction "1_1") (pintype "passive"))
    )
    (net (code "67") (name "WDIN_6") (class "Default")
      (node (ref "J1") (pin "18") (pinfunction "18_18") (pintype "bidirectional"))
      (node (ref "R15") (pin "1") (pinfunction "1_1") (pintype "passive"))
    )
    (net (code "68") (name "WDIN_7") (class "Default")
      (node (ref "J1") (pin "19") (pinfunction "19_19") (pintype "bidirectional"))
      (node (ref "R16") (pin "1") (pinfunction "1_1") (pintype "passive"))
    )
    (net (code "69") (name "WRITE") (class "Default")
      (node (ref "D53") (pin "A") (pinfunction "A_A") (pintype "passive"))
      (node (ref "D54") (pin "C") (pinfunction "C_C") (pintype "passive"))
      (node (ref "J5") (pin "21") (pinfunction "21_21") (pintype "bidirectional"))
      (node (ref "R18") (pin "2") (pinfunction "2_2") (pintype "passive"))
    )
    (net (code "70") (name "WRITEIN") (class "Default")
      (node (ref "J2") (pin "3") (pinfunction "3_3") (pintype "bidirectional"))
      (node (ref "R18") (pin "1") (pinfunction "1_1") (pintype "passive"))
    )
    (net (code "71") (name "unconnected-(J5-Pad40)") (class "Default")
      (node (ref "J5") (pin "40") (pinfunction "40_40") (pintype "bidirectional"))
    )
  )
)
